# JACK_DUAL_M2.net
KiCad netlist of a schematic drawn in EAGLE
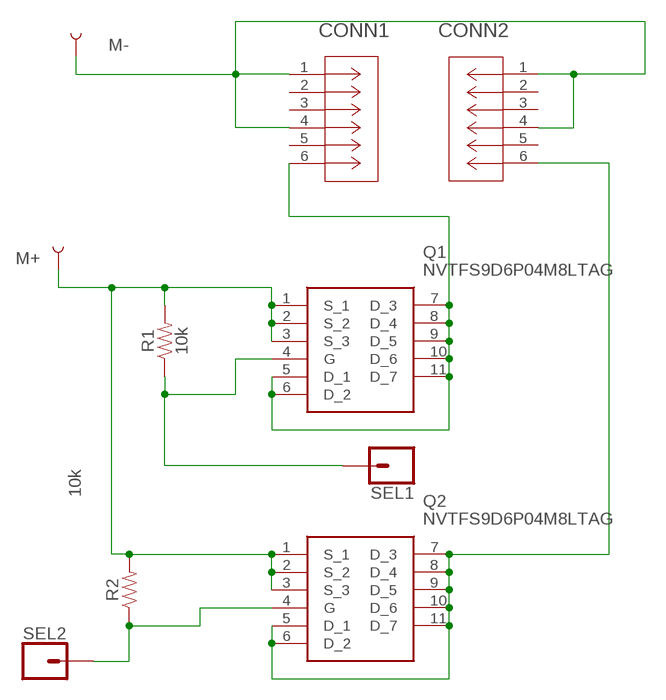
[diagram p0: schematic, sheet 1]

(export (version "E")
  (design (tool "Eeschema 10.0.6"))
  (components
    (comp (ref "CONN1")
      (value "ACJS-MHDR")
      (footprint "eagle-import:CONN_MHDR_AMP")
      (fields (field (name "COPYRIGHT") "Copyright (C) 2018 Accelerated Designs. All rights reserved"))
      (libsource (lib "eagle-import") (part "ACJS-MHDR"))
    )
    (comp (ref "CONN2")
      (value "ACJS-MHDR")
      (footprint "eagle-import:CONN_MHDR_AMP")
      (fields (field (name "COPYRIGHT") "Copyright (C) 2018 Accelerated Designs. All rights reserved"))
      (libsource (lib "eagle-import") (part "ACJS-MHDR"))
    )
    (comp (ref "M+")
      (value "TEST-POINT3")
      (footprint "eagle-import:PAD.03X.03")
      (libsource (lib "eagle-import") (part "TEST-POINT3"))
    )
    (comp (ref "M-")
      (value "TEST-POINT3")
      (footprint "eagle-import:PAD.03X.03")
      (libsource (lib "eagle-import") (part "TEST-POINT3"))
    )
    (comp (ref "Q1")
      (value "NVTFS9D6P04M8LTAG")
      (footprint "eagle-import:NVTFS5124PLTWG")
      (fields (field (name "MOUSER_PART_NUMBER") "863-NVTFS9D6P04M8LTG"))
      (libsource (lib "eagle-import") (part "NVTFS9D6P04M8LTAG"))
    )
    (comp (ref "Q2")
      (value "NVTFS9D6P04M8LTAG")
      (footprint "eagle-import:NVTFS5124PLTWG")
      (fields (field (name "MOUSER_PART_NUMBER") "863-NVTFS9D6P04M8LTG"))
      (libsource (lib "eagle-import") (part "NVTFS9D6P04M8LTAG"))
    )
    (comp (ref "R1")
      (value "10k")
      (footprint "eagle-import:0805")
      (libsource (lib "eagle-import") (part "RESISTOR0805"))
    )
    (comp (ref "R2")
      (value "10k")
      (footprint "eagle-import:0805")
      (libsource (lib "eagle-import") (part "RESISTOR0805"))
    )
    (comp (ref "SEL1")
      (value "CONN_01")
      (footprint "eagle-import:1X01")
      (libsource (lib "eagle-import") (part "CONN_01"))
    )
    (comp (ref "SEL2")
      (value "CONN_01")
      (footprint "eagle-import:1X01")
      (libsource (lib "eagle-import") (part "CONN_01"))
    )
  )
  (nets
    (net (code "1") (name "Net-(M+-1)") (class "Default")
      (node (ref "M+") (pin "P$1") (pinfunction "1_P$1") (pintype "bidirectional"))
      (node (ref "Q1") (pin "1") (pinfunction "S_1_1") (pintype "bidirectional"))
      (node (ref "Q1") (pin "2") (pinfunction "S_2_2") (pintype "bidirectional"))
      (node (ref "Q1") (pin "3") (pinfunction "S_3_3") (pintype "bidirectional"))
      (node (ref "Q2") (pin "1") (pinfunction "S_1_1") (pintype "bidirectional"))
      (node (ref "Q2") (pin "2") (pinfunction "S_2_2") (pintype "bidirectional"))
      (node (ref "Q2") (pin "3") (pinfunction "S_3_3") (pintype "bidirectional"))
      (node (ref "R1") (pin "2") (pinfunction "2_2") (pintype "passive"))
      (node (ref "R2") (pin "2") (pinfunction "2_2") (pintype "passive"))
    )
    (net (code "2") (name "Net-(M--1)") (class "Default")
      (node (ref "CONN1") (pin "1") (pinfunction "1_1") (pintype "passive"))
      (node (ref "CONN1") (pin "4") (pinfunction "4_4") (pintype "passive"))
      (node (ref "CONN2") (pin "1") (pinfunction "1_1") (pintype "passive"))
      (node (ref "CONN2") (pin "4") (pinfunction "4_4") (pintype "passive"))
      (node (ref "M-") (pin "P$1") (pinfunction "1_P$1") (pintype "bidirectional"))
    )
    (net (code "3") (name "Net-(Q1-D_1)") (class "Default")
      (node (ref "CONN1") (pin "6") (pinfunction "6_6") (pintype "passive"))
      (node (ref "Q1") (pin "10") (pinfunction "D_6_10") (pintype "bidirectional"))
      (node (ref "Q1") (pin "11") (pinfunction "D_7_11") (pintype "bidirectional"))
      (node (ref "Q1") (pin "5") (pinfunction "D_1_5") (pintype "bidirectional"))
      (node (ref "Q1") (pin "6") (pinfunction "D_2_6") (pintype "bidirectional"))
      (node (ref "Q1") (pin "7") (pinfunction "D_3_7") (pintype "bidirectional"))
      (node (ref "Q1") (pin "8") (pinfunction "D_4_8") (pintype "bidirectional"))
      (node (ref "Q1") (pin "9") (pinfunction "D_5_9") (pintype "bidirectional"))
    )
    (net (code "4") (name "Net-(Q1-G)") (class "Default")
      (node (ref "Q1") (pin "4") (pinfunction "G_4") (pintype "bidirectional"))
      (node (ref "R1") (pin "1") (pinfunction "1_1") (pintype "passive"))
      (node (ref "SEL1") (pin "1") (pinfunction "1_1") (pintype "passive"))
    )
    (net (code "5") (name "Net-(Q2-D_1)") (class "Default")
      (node (ref "CONN2") (pin "6") (pinfunction "6_6") (pintype "passive"))
      (node (ref "Q2") (pin "10") (pinfunction "D_6_10") (pintype "bidirectional"))
      (node (ref "Q2") (pin "11") (pinfunction "D_7_11") (pintype "bidirectional"))
      (node (ref "Q2") (pin "5") (pinfunction "D_1_5") (pintype "bidirectional"))
      (node (ref "Q2") (pin "6") (pinfunction "D_2_6") (pintype "bidirectional"))
      (node (ref "Q2") (pin "7") (pinfunction "D_3_7") (pintype "bidirectional"))
      (node (ref "Q2") (pin "8") (pinfunction "D_4_8") (pintype "bidirectional"))
      (node (ref "Q2") (pin "9") (pinfunction "D_5_9") (pintype "bidirectional"))
    )
    (net (code "6") (name "Net-(Q2-G)") (class "Default")
      (node (ref "Q2") (pin "4") (pinfunction "G_4") (pintype "bidirectional"))
      (node (ref "R2") (pin "1") (pinfunction "1_1") (pintype "passive"))
      (node (ref "SEL2") (pin "1") (pinfunction "1_1") (pintype "passive"))
    )
    (net (code "7") (name "unconnected-(CONN1-Pad2)") (class "Default")
      (node (ref "CONN1") (pin "2") (pinfunction "2_2") (pintype "passive"))
    )
    (net (code "8") (name "unconnected-(CONN1-Pad3)") (class "Default")
      (node (ref "CONN1") (pin "3") (pinfunction "3_3") (pintype "passive"))
    )
    (net (code "9") (name "unconnected-(CONN1-Pad5)") (class "Default")
      (node (ref "CONN1") (pin "5") (pinfunction "5_5") (pintype "passive"))
    )
    (net (code "10") (name "unconnected-(CONN2-Pad2)") (class "Default")
      (node (ref "CONN2") (pin "2") (pinfunction "2_2") (pintype "passive"))
    )
    (net (code "11") (name "unconnected-(CONN2-Pad3)") (class "Default")
      (node (ref "CONN2") (pin "3") (pinfunction "3_3") (pintype "passive"))
    )
    (net (code "12") (name "unconnected-(CONN2-Pad5)") (class "Default")
      (node (ref "CONN2") (pin "5") (pinfunction "5_5") (pintype "passive"))
    )
  )
)
